# BigTime.net
KiCad netlist of a schematic drawn in EAGLE
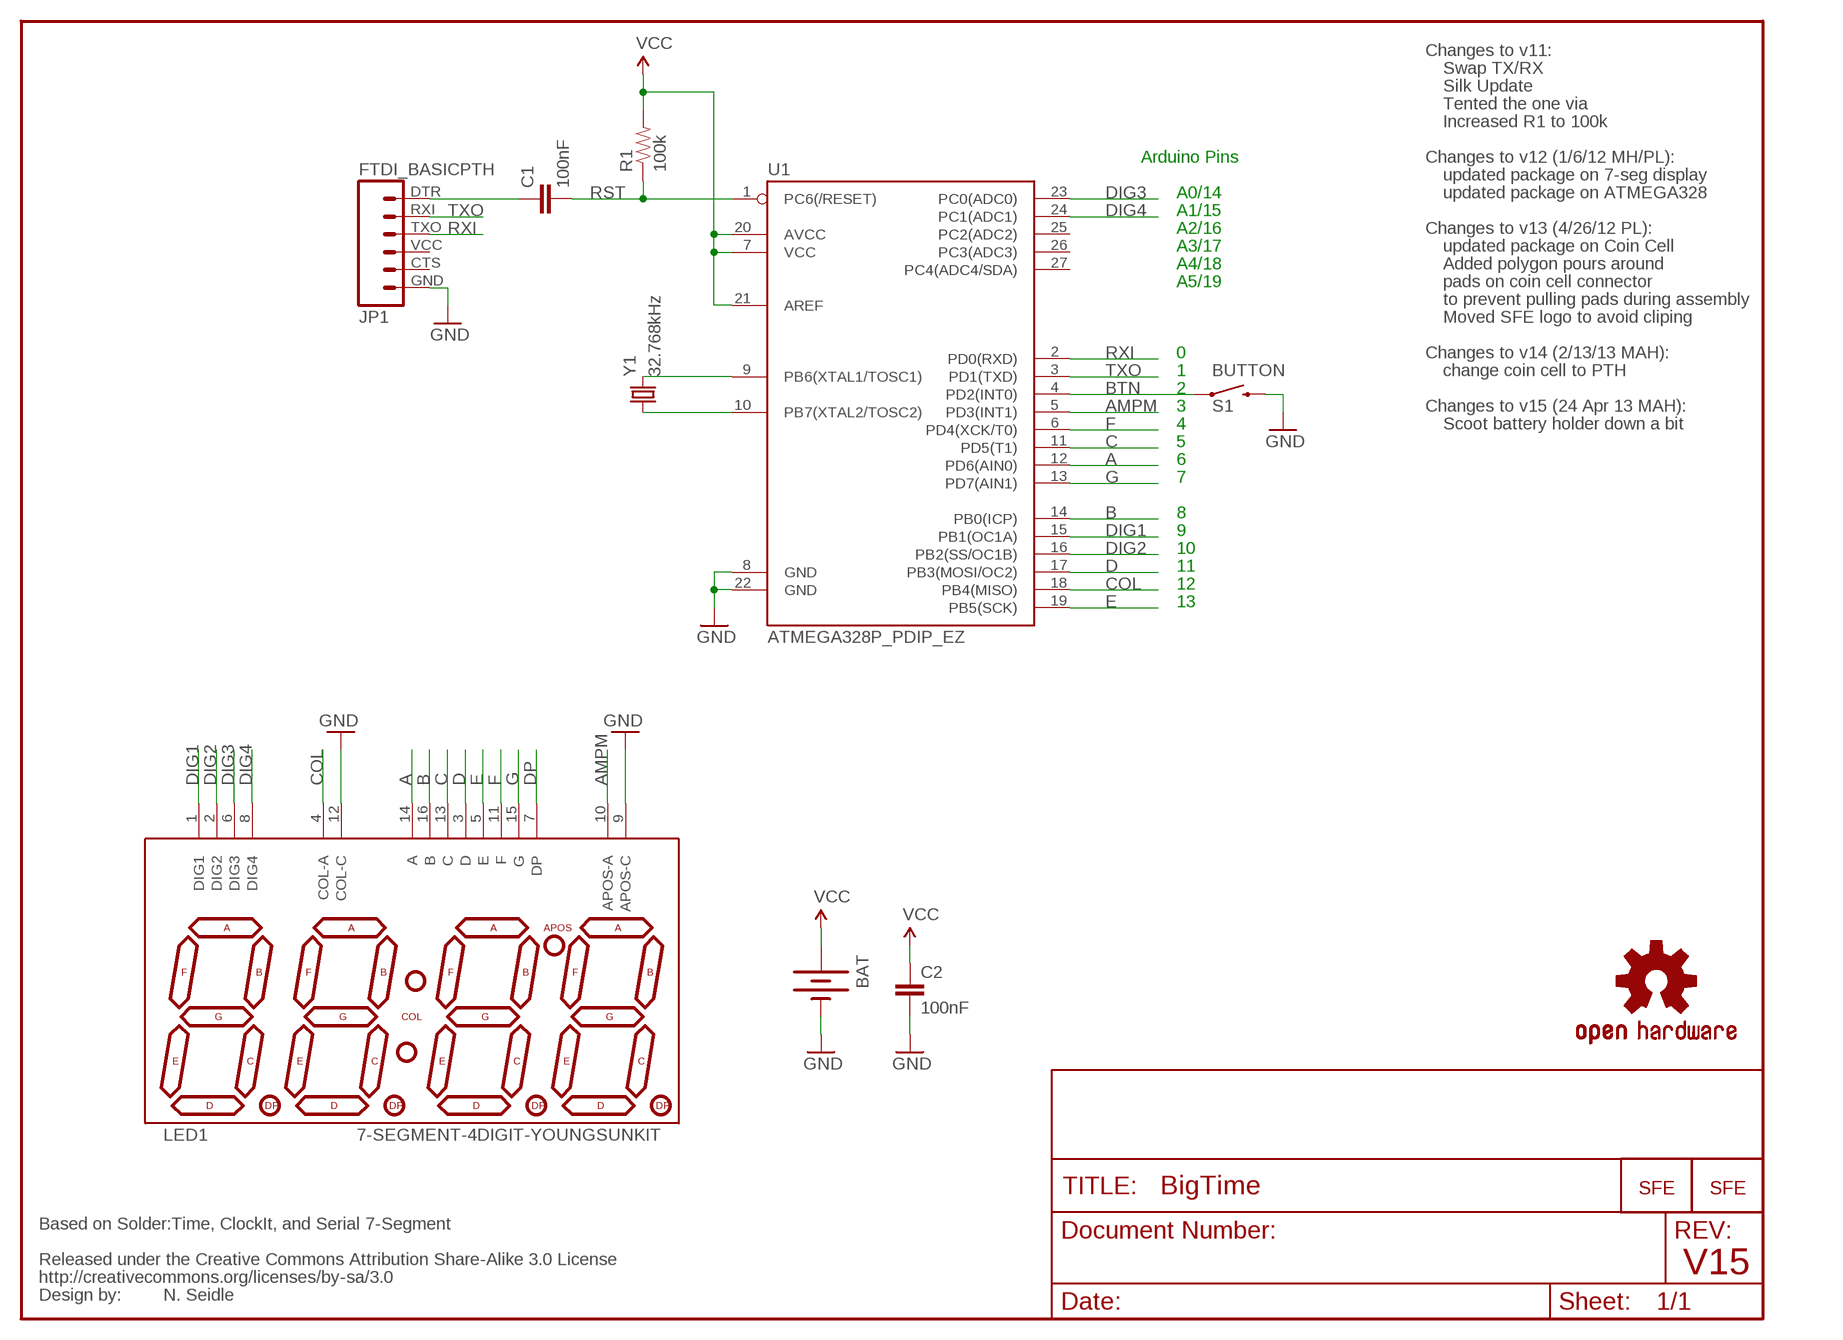
[diagram p0: schematic, sheet 1]

(export (version "E")
  (design (tool "Eeschema 10.0.6"))
  (components
    (comp (ref "BAT")
      (value "BATTERYFOB")
      (footprint "eagle-import:BATTERY_20MM_PTH_COMPACT")
      (libsource (lib "eagle-import") (part "BATTERYFOB"))
    )
    (comp (ref "C1")
      (value "100nF")
      (footprint "eagle-import:CAP-PTH-SMALLEZ")
      (libsource (lib "eagle-import") (part "CAPEZ"))
    )
    (comp (ref "C2")
      (value "100nF")
      (footprint "eagle-import:CAP-PTH-SMALLEZ")
      (libsource (lib "eagle-import") (part "CAPEZ"))
    )
    (comp (ref "JP1")
      (value "FTDI_BASICPTH")
      (footprint "eagle-import:FTDI_BASIC")
      (libsource (lib "eagle-import") (part "FTDI_BASICPTH"))
    )
    (comp (ref "LED1")
      (value "7-SEGMENT-4DIGIT-YOUNGSUNKIT")
      (footprint "eagle-import:7-SEGMENT-4DIGIT-YOUNGSUN-KIT")
      (libsource (lib "eagle-import") (part "7-SEGMENT-4DIGIT-YOUNGSUNKIT"))
    )
    (comp (ref "R1")
      (value "100k")
      (footprint "eagle-import:AXIAL-0.3-KIT")
      (libsource (lib "eagle-import") (part "RESISTORKIT"))
    )
    (comp (ref "S1")
      (value "BUTTON")
      (footprint "eagle-import:TACTILE-PTH-SIDEEZ")
      (libsource (lib "eagle-import") (part "SWITCH-MOMENTARY-2SIDE_EZ"))
    )
    (comp (ref "U$1")
      (value "LOGO-SFESK")
      (footprint "eagle-import:SFE-LOGO-FLAME")
      (libsource (lib "eagle-import") (part "LOGO-SFESK"))
    )
    (comp (ref "U$2")
      (value "CREATIVE_COMMONS")
      (footprint "eagle-import:CREATIVE_COMMONS")
      (libsource (lib "eagle-import") (part "CREATIVE_COMMONS"))
    )
    (comp (ref "U$4")
      (value "OSHW-LOGOS")
      (footprint "eagle-import:OSHW-LOGO-S")
      (libsource (lib "eagle-import") (part "OSHW-LOGOS"))
    )
    (comp (ref "U$5")
      (value "LOGO-SFENW2")
      (footprint "eagle-import:SFE-NEW-WEB")
      (libsource (lib "eagle-import") (part "LOGO-SFENW2"))
    )
    (comp (ref "U1")
      (value "ATMEGA328P_PDIP_EZ")
      (footprint "eagle-import:DIL28-EZ")
      (libsource (lib "eagle-import") (part "ATMEGA328P_PDIP_EZ"))
    )
    (comp (ref "Y1")
      (value "32.768kHz")
      (footprint "eagle-import:TC26HEZ")
      (libsource (lib "eagle-import") (part "CRYSTALTC26H_EZ"))
    )
  )
  (nets
    (net (code "1") (name "/A") (class "Default")
      (node (ref "LED1") (pin "14") (pinfunction "A_14") (pintype "bidirectional"))
      (node (ref "U1") (pin "12") (pinfunction "PD6(AIN0)_12") (pintype "bidirectional"))
    )
    (net (code "2") (name "/AMPM") (class "Default")
      (node (ref "LED1") (pin "10") (pinfunction "APOS-A_10") (pintype "bidirectional"))
      (node (ref "U1") (pin "5") (pinfunction "PD3(INT1)_5") (pintype "bidirectional"))
    )
    (net (code "3") (name "/B") (class "Default")
      (node (ref "LED1") (pin "16") (pinfunction "B_16") (pintype "bidirectional"))
      (node (ref "U1") (pin "14") (pinfunction "PB0(ICP)_14") (pintype "bidirectional"))
    )
    (net (code "4") (name "/BTN") (class "Default")
      (node (ref "S1") (pin "1") (pinfunction "1_1") (pintype "passive"))
      (node (ref "U1") (pin "4") (pinfunction "PD2(INT0)_4") (pintype "bidirectional"))
    )
    (net (code "5") (name "/C") (class "Default")
      (node (ref "LED1") (pin "13") (pinfunction "C_13") (pintype "bidirectional"))
      (node (ref "U1") (pin "11") (pinfunction "PD5(T1)_11") (pintype "bidirectional"))
    )
    (net (code "6") (name "/COL") (class "Default")
      (node (ref "LED1") (pin "4") (pinfunction "COL-A_4") (pintype "bidirectional"))
      (node (ref "U1") (pin "18") (pinfunction "PB4(MISO)_18") (pintype "bidirectional"))
    )
    (net (code "7") (name "/D") (class "Default")
      (node (ref "LED1") (pin "3") (pinfunction "D_3") (pintype "bidirectional"))
      (node (ref "U1") (pin "17") (pinfunction "PB3(MOSI/OC2)_17") (pintype "bidirectional"))
    )
    (net (code "8") (name "/DIG1") (class "Default")
      (node (ref "LED1") (pin "1") (pinfunction "DIG1_1") (pintype "bidirectional"))
      (node (ref "U1") (pin "15") (pinfunction "PB1(OC1A)_15") (pintype "bidirectional"))
    )
    (net (code "9") (name "/DIG2") (class "Default")
      (node (ref "LED1") (pin "2") (pinfunction "DIG2_2") (pintype "bidirectional"))
      (node (ref "U1") (pin "16") (pinfunction "PB2(SS/OC1B)_16") (pintype "bidirectional"))
    )
    (net (code "10") (name "/DIG3") (class "Default")
      (node (ref "LED1") (pin "6") (pinfunction "DIG3_6") (pintype "bidirectional"))
      (node (ref "U1") (pin "23") (pinfunction "PC0(ADC0)_23") (pintype "bidirectional"))
    )
    (net (code "11") (name "/DIG4") (class "Default")
      (node (ref "LED1") (pin "8") (pinfunction "DIG4_8") (pintype "bidirectional"))
      (node (ref "U1") (pin "24") (pinfunction "PC1(ADC1)_24") (pintype "bidirectional"))
    )
    (net (code "12") (name "/DP") (class "Default")
      (node (ref "LED1") (pin "7") (pinfunction "DP_7") (pintype "bidirectional"))
    )
    (net (code "13") (name "/E") (class "Default")
      (node (ref "LED1") (pin "5") (pinfunction "E_5") (pintype "bidirectional"))
      (node (ref "U1") (pin "19") (pinfunction "PB5(SCK)_19") (pintype "bidirectional"))
    )
    (net (code "14") (name "/F") (class "Default")
      (node (ref "LED1") (pin "11") (pinfunction "F_11") (pintype "bidirectional"))
      (node (ref "U1") (pin "6") (pinfunction "PD4(XCK/T0)_6") (pintype "bidirectional"))
    )
    (net (code "15") (name "/G") (class "Default")
      (node (ref "LED1") (pin "15") (pinfunction "G_15") (pintype "bidirectional"))
      (node (ref "U1") (pin "13") (pinfunction "PD7(AIN1)_13") (pintype "bidirectional"))
    )
    (net (code "16") (name "/RST") (class "Default")
      (node (ref "C1") (pin "2") (pinfunction "2_2") (pintype "passive"))
      (node (ref "R1") (pin "P$1") (pinfunction "1_P$1") (pintype "passive"))
      (node (ref "U1") (pin "1") (pinfunction "PC6(/RESET)_1") (pintype "bidirectional"))
    )
    (net (code "17") (name "/RXI") (class "Default")
      (node (ref "JP1") (pin "TXO") (pinfunction "3_TXO") (pintype "passive"))
      (node (ref "U1") (pin "2") (pinfunction "PD0(RXD)_2") (pintype "bidirectional"))
    )
    (net (code "18") (name "/TXO") (class "Default")
      (node (ref "JP1") (pin "RXI") (pinfunction "2_RXI") (pintype "passive"))
      (node (ref "U1") (pin "3") (pinfunction "PD1(TXD)_3") (pintype "bidirectional"))
    )
    (net (code "19") (name "GND") (class "Default")
      (node (ref "BAT") (pin "2") (pinfunction "-_2") (pintype "power_in"))
      (node (ref "C2") (pin "2") (pinfunction "2_2") (pintype "passive"))
      (node (ref "JP1") (pin "GND") (pinfunction "6_GND") (pintype "passive"))
      (node (ref "LED1") (pin "12") (pinfunction "COL-C_12") (pintype "bidirectional"))
      (node (ref "LED1") (pin "9") (pinfunction "APOS-C_9") (pintype "bidirectional"))
      (node (ref "S1") (pin "2") (pinfunction "2_2") (pintype "passive"))
      (node (ref "U1") (pin "22") (pinfunction "GND_22") (pintype "bidirectional"))
      (node (ref "U1") (pin "8") (pinfunction "GND_8") (pintype "bidirectional"))
    )
    (net (code "20") (name "Net-(JP1-1)") (class "Default")
      (node (ref "C1") (pin "1") (pinfunction "1_1") (pintype "passive"))
      (node (ref "JP1") (pin "DTR") (pinfunction "1_DTR") (pintype "passive"))
    )
    (net (code "21") (name "Net-(U1-PB6(XTAL1{slash}TOSC1))") (class "Default")
      (node (ref "U1") (pin "9") (pinfunction "PB6(XTAL1/TOSC1)_9") (pintype "bidirectional"))
      (node (ref "Y1") (pin "2") (pinfunction "2_2") (pintype "passive"))
    )
    (net (code "22") (name "Net-(U1-PB7(XTAL2{slash}TOSC2))") (class "Default")
      (node (ref "U1") (pin "10") (pinfunction "PB7(XTAL2/TOSC2)_10") (pintype "bidirectional"))
      (node (ref "Y1") (pin "1") (pinfunction "1_1") (pintype "passive"))
    )
    (net (code "23") (name "VCC") (class "Default")
      (node (ref "BAT") (pin "1") (pinfunction "+_1") (pintype "power_in"))
      (node (ref "C2") (pin "1") (pinfunction "1_1") (pintype "passive"))
      (node (ref "R1") (pin "P$2") (pinfunction "2_P$2") (pintype "passive"))
      (node (ref "U1") (pin "20") (pinfunction "AVCC_20") (pintype "bidirectional"))
      (node (ref "U1") (pin "21") (pinfunction "AREF_21") (pintype "bidirectional"))
      (node (ref "U1") (pin "7") (pinfunction "VCC_7") (pintype "bidirectional"))
    )
    (net (code "24") (name "unconnected-(JP1-4-PadVCC)") (class "Default")
      (node (ref "JP1") (pin "VCC") (pinfunction "4_VCC") (pintype "passive"))
    )
    (net (code "25") (name "unconnected-(JP1-5-PadCTS)") (class "Default")
      (node (ref "JP1") (pin "CTS") (pinfunction "5_CTS") (pintype "passive"))
    )
    (net (code "26") (name "unconnected-(U1-PC2(ADC2)-Pad25)") (class "Default")
      (node (ref "U1") (pin "25") (pinfunction "PC2(ADC2)_25") (pintype "bidirectional"))
    )
    (net (code "27") (name "unconnected-(U1-PC3(ADC3)-Pad26)") (class "Default")
      (node (ref "U1") (pin "26") (pinfunction "PC3(ADC3)_26") (pintype "bidirectional"))
    )
    (net (code "28") (name "unconnected-(U1-PC4(ADC4{slash}SDA)-Pad27)") (class "Default")
      (node (ref "U1") (pin "27") (pinfunction "PC4(ADC4/SDA)_27") (pintype "bidirectional"))
    )
  )
)
